# Dendro.net
KiCad netlist of a schematic drawn in EAGLE
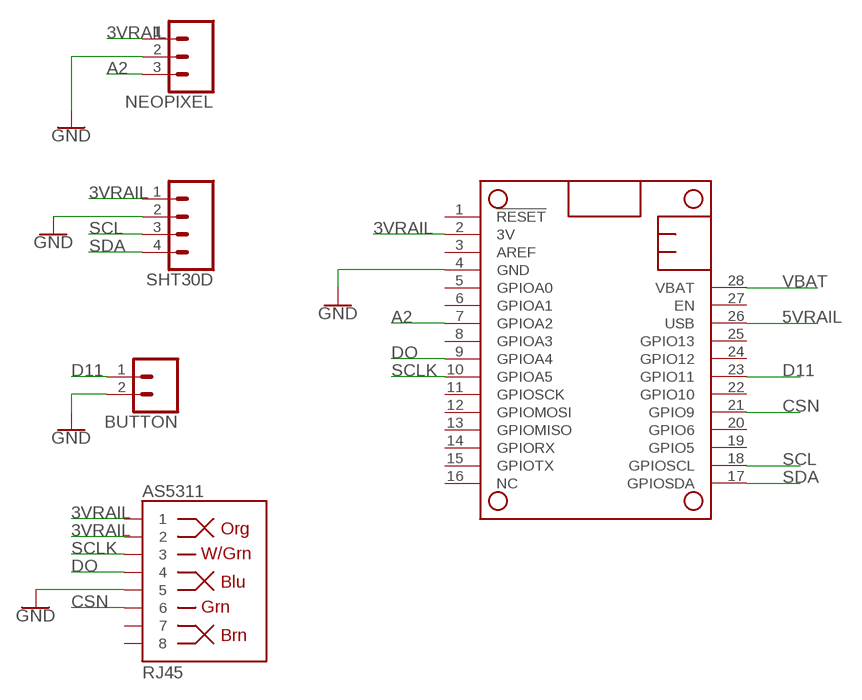
[diagram p0: schematic, sheet 1]

(export (version "E")
  (design (tool "Eeschema 10.0.6"))
  (components
    (comp (ref "AS5311")
      (value "RJ45")
      (footprint "eagle-import:RJ45-8")
      (libsource (lib "eagle-import") (part "RJ45-8"))
    )
    (comp (ref "BUTTON")
      (value "CONN_02")
      (footprint "eagle-import:1X02")
      (libsource (lib "eagle-import") (part "CONN_02"))
    )
    (comp (ref "MS1")
      (value "FEATHERWING")
      (footprint "eagle-import:FEATHERWING")
      (libsource (lib "eagle-import") (part "FEATHERWING"))
    )
    (comp (ref "NEOPIXEL")
      (value "CONN_03")
      (footprint "eagle-import:1X03")
      (libsource (lib "eagle-import") (part "CONN_03"))
    )
    (comp (ref "SHT30D")
      (value "CONN_04")
      (footprint "eagle-import:1X04")
      (libsource (lib "eagle-import") (part "CONN_04"))
    )
  )
  (nets
    (net (code "1") (name "/3VRAIL") (class "Default")
      (node (ref "AS5311") (pin "1") (pinfunction "1_1") (pintype "bidirectional"))
      (node (ref "AS5311") (pin "2") (pinfunction "2_2") (pintype "bidirectional"))
      (node (ref "MS1") (pin "2") (pinfunction "3V_2") (pintype "power_in"))
      (node (ref "NEOPIXEL") (pin "1") (pinfunction "1_1") (pintype "passive"))
      (node (ref "SHT30D") (pin "1") (pinfunction "1_1") (pintype "passive"))
    )
    (net (code "2") (name "/5VRAIL") (class "Default")
      (node (ref "MS1") (pin "26") (pinfunction "USB_26") (pintype "power_in"))
    )
    (net (code "3") (name "/A2") (class "Default")
      (node (ref "MS1") (pin "7") (pinfunction "GPIOA2_7") (pintype "bidirectional"))
      (node (ref "NEOPIXEL") (pin "3") (pinfunction "3_3") (pintype "passive"))
    )
    (net (code "4") (name "/CSN") (class "Default")
      (node (ref "AS5311") (pin "6") (pinfunction "6_6") (pintype "bidirectional"))
      (node (ref "MS1") (pin "21") (pinfunction "GPIO9_21") (pintype "bidirectional"))
    )
    (net (code "5") (name "/D11") (class "Default")
      (node (ref "BUTTON") (pin "1") (pinfunction "1_1") (pintype "passive"))
      (node (ref "MS1") (pin "23") (pinfunction "GPIO11_23") (pintype "bidirectional"))
    )
    (net (code "6") (name "/DO") (class "Default")
      (node (ref "AS5311") (pin "4") (pinfunction "4_4") (pintype "bidirectional"))
      (node (ref "MS1") (pin "9") (pinfunction "GPIOA4_9") (pintype "bidirectional"))
    )
    (net (code "7") (name "/SCL") (class "Default")
      (node (ref "MS1") (pin "18") (pinfunction "GPIOSCL_18") (pintype "bidirectional"))
      (node (ref "SHT30D") (pin "3") (pinfunction "3_3") (pintype "passive"))
    )
    (net (code "8") (name "/SCLK") (class "Default")
      (node (ref "AS5311") (pin "3") (pinfunction "3_3") (pintype "bidirectional"))
      (node (ref "MS1") (pin "10") (pinfunction "GPIOA5_10") (pintype "bidirectional"))
    )
    (net (code "9") (name "/SDA") (class "Default")
      (node (ref "MS1") (pin "17") (pinfunction "GPIOSDA_17") (pintype "bidirectional"))
      (node (ref "SHT30D") (pin "4") (pinfunction "4_4") (pintype "passive"))
    )
    (net (code "10") (name "/VBAT") (class "Default")
      (node (ref "MS1") (pin "28") (pinfunction "VBAT_28") (pintype "power_in"))
    )
    (net (code "11") (name "GND") (class "Default")
      (node (ref "AS5311") (pin "5") (pinfunction "5_5") (pintype "bidirectional"))
      (node (ref "BUTTON") (pin "2") (pinfunction "2_2") (pintype "passive"))
      (node (ref "MS1") (pin "4") (pinfunction "GND_4") (pintype "power_in"))
      (node (ref "NEOPIXEL") (pin "2") (pinfunction "2_2") (pintype "passive"))
      (node (ref "SHT30D") (pin "2") (pinfunction "2_2") (pintype "passive"))
    )
    (net (code "12") (name "unconnected-(AS5311-Pad7)") (class "Default")
      (node (ref "AS5311") (pin "7") (pinfunction "7_7") (pintype "bidirectional"))
    )
    (net (code "13") (name "unconnected-(AS5311-Pad8)") (class "Default")
      (node (ref "AS5311") (pin "8") (pinfunction "8_8") (pintype "bidirectional"))
    )
    (net (code "14") (name "unconnected-(MS1-AREF-Pad3)") (class "Default")
      (node (ref "MS1") (pin "3") (pinfunction "AREF_3") (pintype "passive"))
    )
    (net (code "15") (name "unconnected-(MS1-EN-Pad27)") (class "Default")
      (node (ref "MS1") (pin "27") (pinfunction "EN_27") (pintype "passive"))
    )
    (net (code "16") (name "unconnected-(MS1-GPIO5-Pad19)") (class "Default")
      (node (ref "MS1") (pin "19") (pinfunction "GPIO5_19") (pintype "bidirectional"))
    )
    (net (code "17") (name "unconnected-(MS1-GPIO6-Pad20)") (class "Default")
      (node (ref "MS1") (pin "20") (pinfunction "GPIO6_20") (pintype "bidirectional"))
    )
    (net (code "18") (name "unconnected-(MS1-GPIO10-Pad22)") (class "Default")
      (node (ref "MS1") (pin "22") (pinfunction "GPIO10_22") (pintype "bidirectional"))
    )
    (net (code "19") (name "unconnected-(MS1-GPIO12-Pad24)") (class "Default")
      (node (ref "MS1") (pin "24") (pinfunction "GPIO12_24") (pintype "bidirectional"))
    )
    (net (code "20") (name "unconnected-(MS1-GPIO13-Pad25)") (class "Default")
      (node (ref "MS1") (pin "25") (pinfunction "GPIO13_25") (pintype "bidirectional"))
    )
    (net (code "21") (name "unconnected-(MS1-GPIOA0-Pad5)") (class "Default")
      (node (ref "MS1") (pin "5") (pinfunction "GPIOA0_5") (pintype "bidirectional"))
    )
    (net (code "22") (name "unconnected-(MS1-GPIOA1-Pad6)") (class "Default")
      (node (ref "MS1") (pin "6") (pinfunction "GPIOA1_6") (pintype "bidirectional"))
    )
    (net (code "23") (name "unconnected-(MS1-GPIOA3-Pad8)") (class "Default")
      (node (ref "MS1") (pin "8") (pinfunction "GPIOA3_8") (pintype "bidirectional"))
    )
    (net (code "24") (name "unconnected-(MS1-GPIOMISO-Pad13)") (class "Default")
      (node (ref "MS1") (pin "13") (pinfunction "GPIOMISO_13") (pintype "bidirectional"))
    )
    (net (code "25") (name "unconnected-(MS1-GPIOMOSI-Pad12)") (class "Default")
      (node (ref "MS1") (pin "12") (pinfunction "GPIOMOSI_12") (pintype "bidirectional"))
    )
    (net (code "26") (name "unconnected-(MS1-GPIORX-Pad14)") (class "Default")
      (node (ref "MS1") (pin "14") (pinfunction "GPIORX_14") (pintype "bidirectional"))
    )
    (net (code "27") (name "unconnected-(MS1-GPIOSCK-Pad11)") (class "Default")
      (node (ref "MS1") (pin "11") (pinfunction "GPIOSCK_11") (pintype "bidirectional"))
    )
    (net (code "28") (name "unconnected-(MS1-GPIOTX-Pad15)") (class "Default")
      (node (ref "MS1") (pin "15") (pinfunction "GPIOTX_15") (pintype "bidirectional"))
    )
    (net (code "29") (name "unconnected-(MS1-NC-Pad16)") (class "Default")
      (node (ref "MS1") (pin "16") (pinfunction "NC_16") (pintype "passive"))
    )
    (net (code "30") (name "unconnected-(MS1-~{RESET}-Pad1)") (class "Default")
      (node (ref "MS1") (pin "1") (pinfunction "~{RESET}_1") (pintype "input"))
    )
  )
)
